# Adafruit_ADXL345_Triple-Axis_Acceleromet.net
KiCad netlist of a schematic drawn in EAGLE
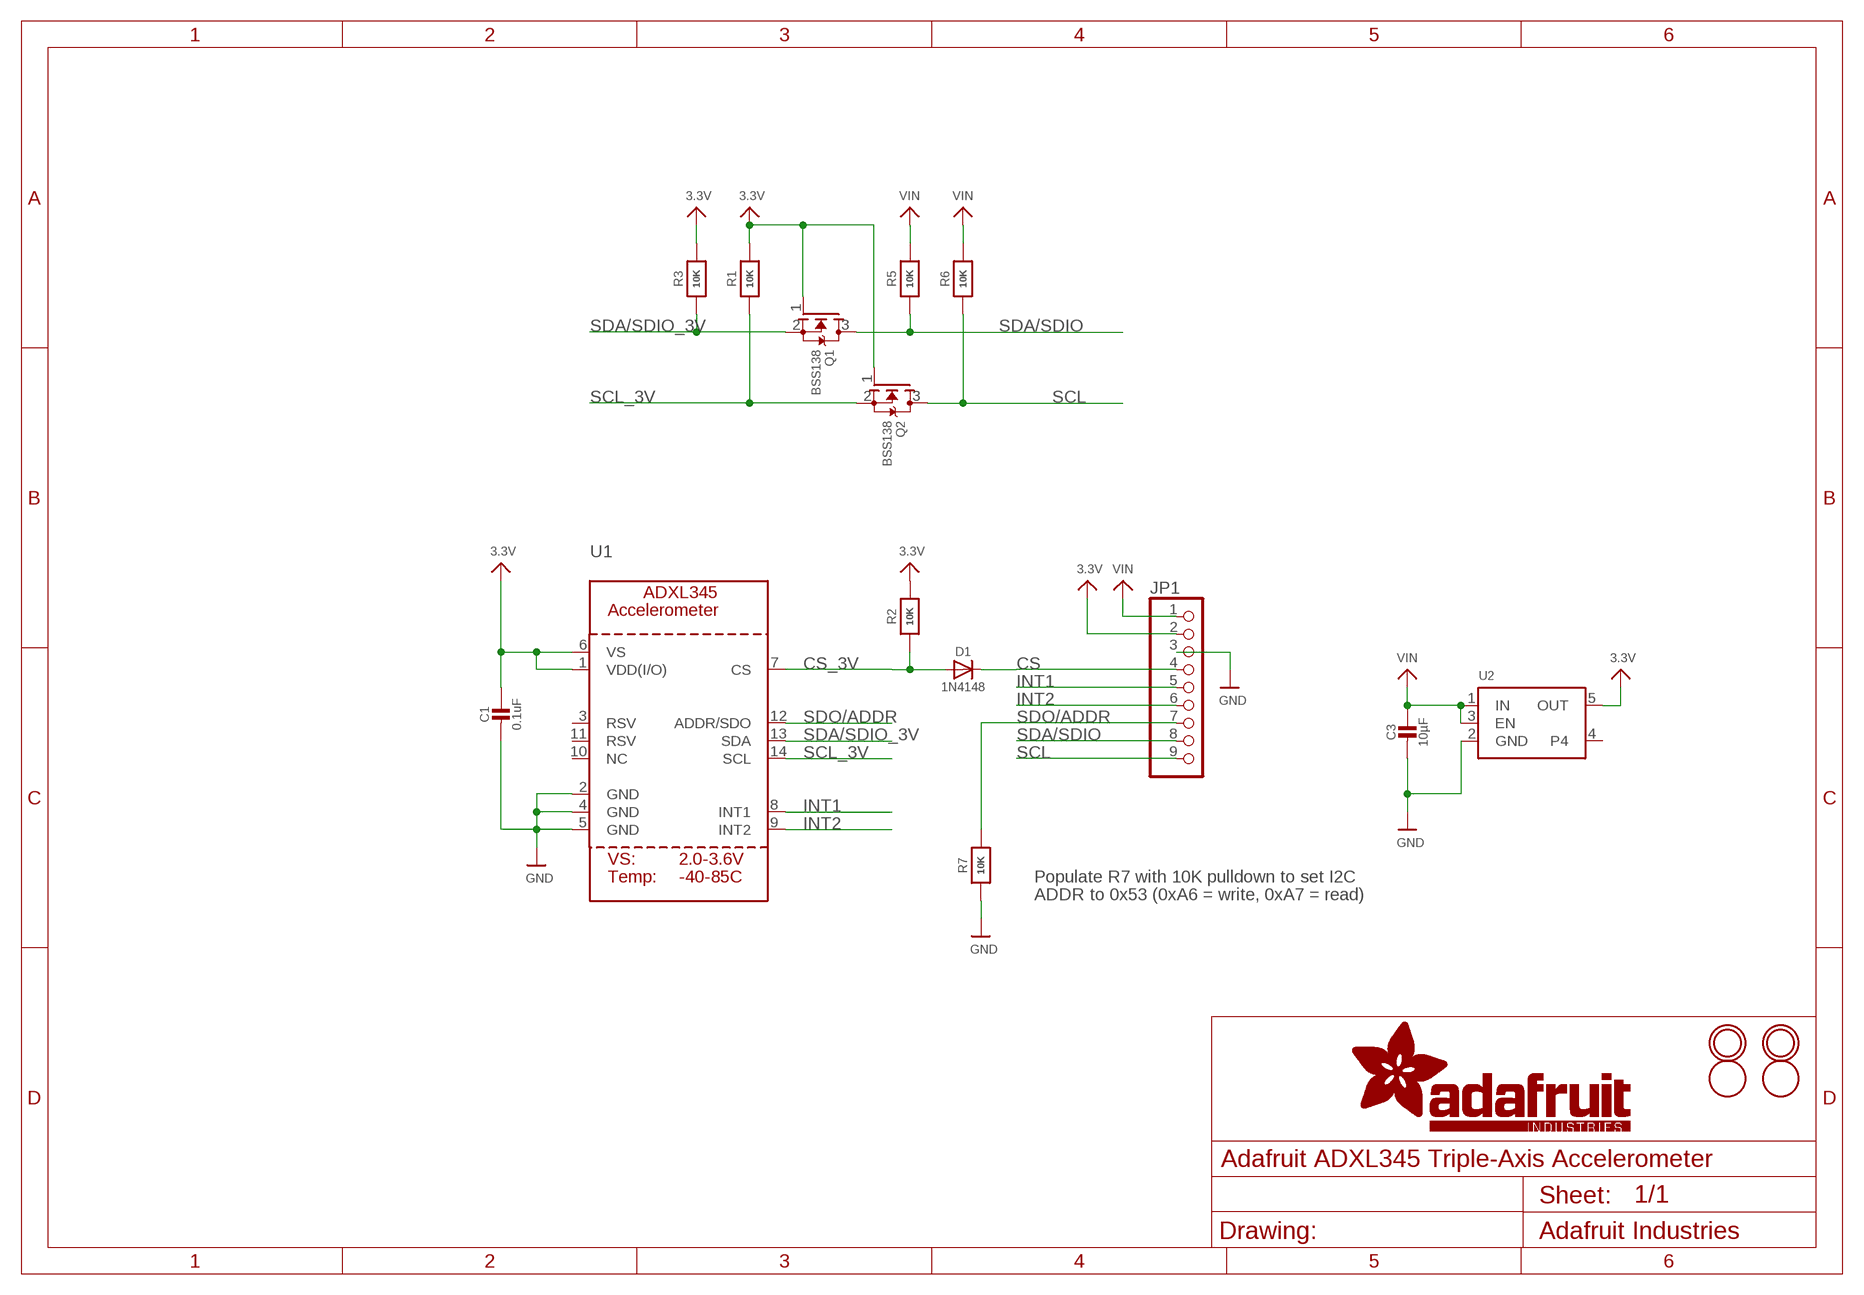
[diagram p0: schematic, sheet 1]

(export (version "E")
  (design (tool "Eeschema 10.0.6"))
  (components
    (comp (ref "C1")
      (value "0.1uF")
      (footprint "eagle-import:0805-NO")
      (libsource (lib "eagle-import") (part "CAP_CERAMIC0805-NOOUTLINE"))
    )
    (comp (ref "C3")
      (value "10µF")
      (footprint "eagle-import:0805-NO")
      (libsource (lib "eagle-import") (part "CAP_CERAMIC0805-NOOUTLINE"))
    )
    (comp (ref "D1")
      (value "1N4148")
      (footprint "eagle-import:SOD-323_MINI")
      (libsource (lib "eagle-import") (part "DIODE_SOD323MINI"))
    )
    (comp (ref "JP1")
      (value "HEADER-1X970MIL")
      (footprint "eagle-import:1X09_ROUND_70")
      (libsource (lib "eagle-import") (part "HEADER-1X970MIL"))
    )
    (comp (ref "Q1")
      (value "BSS138")
      (footprint "eagle-import:SOT23-WIDE")
      (libsource (lib "eagle-import") (part "MOSFET-NWIDE"))
    )
    (comp (ref "Q2")
      (value "BSS138")
      (footprint "eagle-import:SOT23-WIDE")
      (libsource (lib "eagle-import") (part "MOSFET-NWIDE"))
    )
    (comp (ref "R1")
      (value "10K")
      (footprint "eagle-import:0805-NO")
      (libsource (lib "eagle-import") (part "RESISTOR0805_NOOUTLINE"))
    )
    (comp (ref "R2")
      (value "10K")
      (footprint "eagle-import:0805-NO")
      (libsource (lib "eagle-import") (part "RESISTOR0805_NOOUTLINE"))
    )
    (comp (ref "R3")
      (value "10K")
      (footprint "eagle-import:0805-NO")
      (libsource (lib "eagle-import") (part "RESISTOR0805_NOOUTLINE"))
    )
    (comp (ref "R5")
      (value "10K")
      (footprint "eagle-import:0805-NO")
      (libsource (lib "eagle-import") (part "RESISTOR0805_NOOUTLINE"))
    )
    (comp (ref "R6")
      (value "10K")
      (footprint "eagle-import:0805-NO")
      (libsource (lib "eagle-import") (part "RESISTOR0805_NOOUTLINE"))
    )
    (comp (ref "R7")
      (value "10K")
      (footprint "eagle-import:0805-NO")
      (libsource (lib "eagle-import") (part "RESISTOR0805_NOOUTLINE"))
    )
    (comp (ref "U$1")
      (value "FIDUCIAL")
      (footprint "eagle-import:FIDUCIAL_1MM")
      (libsource (lib "eagle-import") (part "FIDUCIAL"))
    )
    (comp (ref "U$3")
      (value "FIDUCIAL")
      (footprint "eagle-import:FIDUCIAL_1MM")
      (libsource (lib "eagle-import") (part "FIDUCIAL"))
    )
    (comp (ref "U$4")
      (value "MOUNTINGHOLE2.5")
      (footprint "eagle-import:MOUNTINGHOLE_2.5_PLATED")
      (libsource (lib "eagle-import") (part "MOUNTINGHOLE2.5"))
    )
    (comp (ref "U$6")
      (value "MOUNTINGHOLE2.5")
      (footprint "eagle-import:MOUNTINGHOLE_2.5_PLATED")
      (libsource (lib "eagle-import") (part "MOUNTINGHOLE2.5"))
    )
    (comp (ref "U1")
      (value "ACCEL_ADXL345")
      (footprint "eagle-import:LGA14")
      (libsource (lib "eagle-import") (part "ACCEL_ADXL345"))
    )
    (comp (ref "U2")
      (value "VREG_SOT23-5")
      (footprint "eagle-import:SOT23-5")
      (libsource (lib "eagle-import") (part "VREG_SOT23-5"))
    )
  )
  (nets
    (net (code "1") (name "/CS") (class "Default")
      (node (ref "D1") (pin "C") (pinfunction "C_C") (pintype "passive"))
      (node (ref "JP1") (pin "4") (pinfunction "4_4") (pintype "passive"))
    )
    (net (code "2") (name "/CS_3V") (class "Default")
      (node (ref "D1") (pin "A") (pinfunction "A_A") (pintype "passive"))
      (node (ref "R2") (pin "1") (pinfunction "1_1") (pintype "passive"))
      (node (ref "U1") (pin "7") (pinfunction "CS_7") (pintype "bidirectional"))
    )
    (net (code "3") (name "/INT1") (class "Default")
      (node (ref "JP1") (pin "5") (pinfunction "5_5") (pintype "passive"))
      (node (ref "U1") (pin "8") (pinfunction "INT1_8") (pintype "bidirectional"))
    )
    (net (code "4") (name "/INT2") (class "Default")
      (node (ref "JP1") (pin "6") (pinfunction "6_6") (pintype "passive"))
      (node (ref "U1") (pin "9") (pinfunction "INT2_9") (pintype "bidirectional"))
    )
    (net (code "5") (name "/SCL") (class "Default")
      (node (ref "JP1") (pin "9") (pinfunction "9_9") (pintype "passive"))
      (node (ref "Q2") (pin "3") (pinfunction "D_3") (pintype "bidirectional"))
      (node (ref "R6") (pin "1") (pinfunction "1_1") (pintype "passive"))
    )
    (net (code "6") (name "/SCL_3V") (class "Default")
      (node (ref "Q2") (pin "2") (pinfunction "S_2") (pintype "bidirectional"))
      (node (ref "R1") (pin "1") (pinfunction "1_1") (pintype "passive"))
      (node (ref "U1") (pin "14") (pinfunction "SCL_14") (pintype "bidirectional"))
    )
    (net (code "7") (name "/SDA{slash}SDIO") (class "Default")
      (node (ref "JP1") (pin "8") (pinfunction "8_8") (pintype "passive"))
      (node (ref "Q1") (pin "3") (pinfunction "D_3") (pintype "bidirectional"))
      (node (ref "R5") (pin "1") (pinfunction "1_1") (pintype "passive"))
    )
    (net (code "8") (name "/SDA{slash}SDIO_3V") (class "Default")
      (node (ref "Q1") (pin "2") (pinfunction "S_2") (pintype "bidirectional"))
      (node (ref "R3") (pin "1") (pinfunction "1_1") (pintype "passive"))
      (node (ref "U1") (pin "13") (pinfunction "SDA_13") (pintype "bidirectional"))
    )
    (net (code "9") (name "/SDO{slash}ADDR") (class "Default")
      (node (ref "JP1") (pin "7") (pinfunction "7_7") (pintype "passive"))
      (node (ref "R7") (pin "2") (pinfunction "2_2") (pintype "passive"))
      (node (ref "U1") (pin "12") (pinfunction "ADDR/SDO_12") (pintype "bidirectional"))
    )
    (net (code "10") (name "3.3V") (class "Default")
      (node (ref "C1") (pin "1") (pinfunction "1_1") (pintype "passive"))
      (node (ref "JP1") (pin "2") (pinfunction "2_2") (pintype "passive"))
      (node (ref "Q1") (pin "1") (pinfunction "G_1") (pintype "bidirectional"))
      (node (ref "Q2") (pin "1") (pinfunction "G_1") (pintype "bidirectional"))
      (node (ref "R1") (pin "2") (pinfunction "2_2") (pintype "passive"))
      (node (ref "R2") (pin "2") (pinfunction "2_2") (pintype "passive"))
      (node (ref "R3") (pin "2") (pinfunction "2_2") (pintype "passive"))
      (node (ref "U1") (pin "1") (pinfunction "VDD(I/O)_1") (pintype "bidirectional"))
      (node (ref "U1") (pin "6") (pinfunction "VS_6") (pintype "bidirectional"))
      (node (ref "U2") (pin "5") (pinfunction "OUT_5") (pintype "power_in"))
    )
    (net (code "11") (name "GND") (class "Default")
      (node (ref "C1") (pin "2") (pinfunction "2_2") (pintype "passive"))
      (node (ref "C3") (pin "2") (pinfunction "2_2") (pintype "passive"))
      (node (ref "JP1") (pin "3") (pinfunction "3_3") (pintype "passive"))
      (node (ref "R7") (pin "1") (pinfunction "1_1") (pintype "passive"))
      (node (ref "U1") (pin "2") (pinfunction "GND_2") (pintype "bidirectional"))
      (node (ref "U1") (pin "4") (pinfunction "GND_4") (pintype "bidirectional"))
      (node (ref "U1") (pin "5") (pinfunction "GND_5") (pintype "bidirectional"))
      (node (ref "U2") (pin "2") (pinfunction "GND_2") (pintype "power_in"))
    )
    (net (code "12") (name "VIN") (class "Default")
      (node (ref "C3") (pin "1") (pinfunction "1_1") (pintype "passive"))
      (node (ref "JP1") (pin "1") (pinfunction "1_1") (pintype "passive"))
      (node (ref "R5") (pin "2") (pinfunction "2_2") (pintype "passive"))
      (node (ref "R6") (pin "2") (pinfunction "2_2") (pintype "passive"))
      (node (ref "U2") (pin "1") (pinfunction "IN_1") (pintype "power_in"))
      (node (ref "U2") (pin "3") (pinfunction "EN_3") (pintype "input"))
    )
    (net (code "13") (name "unconnected-(U1-NC-Pad10)") (class "Default")
      (node (ref "U1") (pin "10") (pinfunction "NC_10") (pintype "bidirectional"))
    )
    (net (code "14") (name "unconnected-(U1-RSV-Pad3)") (class "Default")
      (node (ref "U1") (pin "3") (pinfunction "RSV_3") (pintype "bidirectional"))
    )
    (net (code "15") (name "unconnected-(U1-RSV-Pad11)") (class "Default")
      (node (ref "U1") (pin "11") (pinfunction "RSV_11") (pintype "bidirectional"))
    )
    (net (code "16") (name "unconnected-(U2-P4-Pad4)") (class "Default")
      (node (ref "U2") (pin "4") (pinfunction "P4_4") (pintype "bidirectional"))
    )
  )
)
